# BatteryBoard.net
KiCad netlist of a schematic drawn in Altium Designer
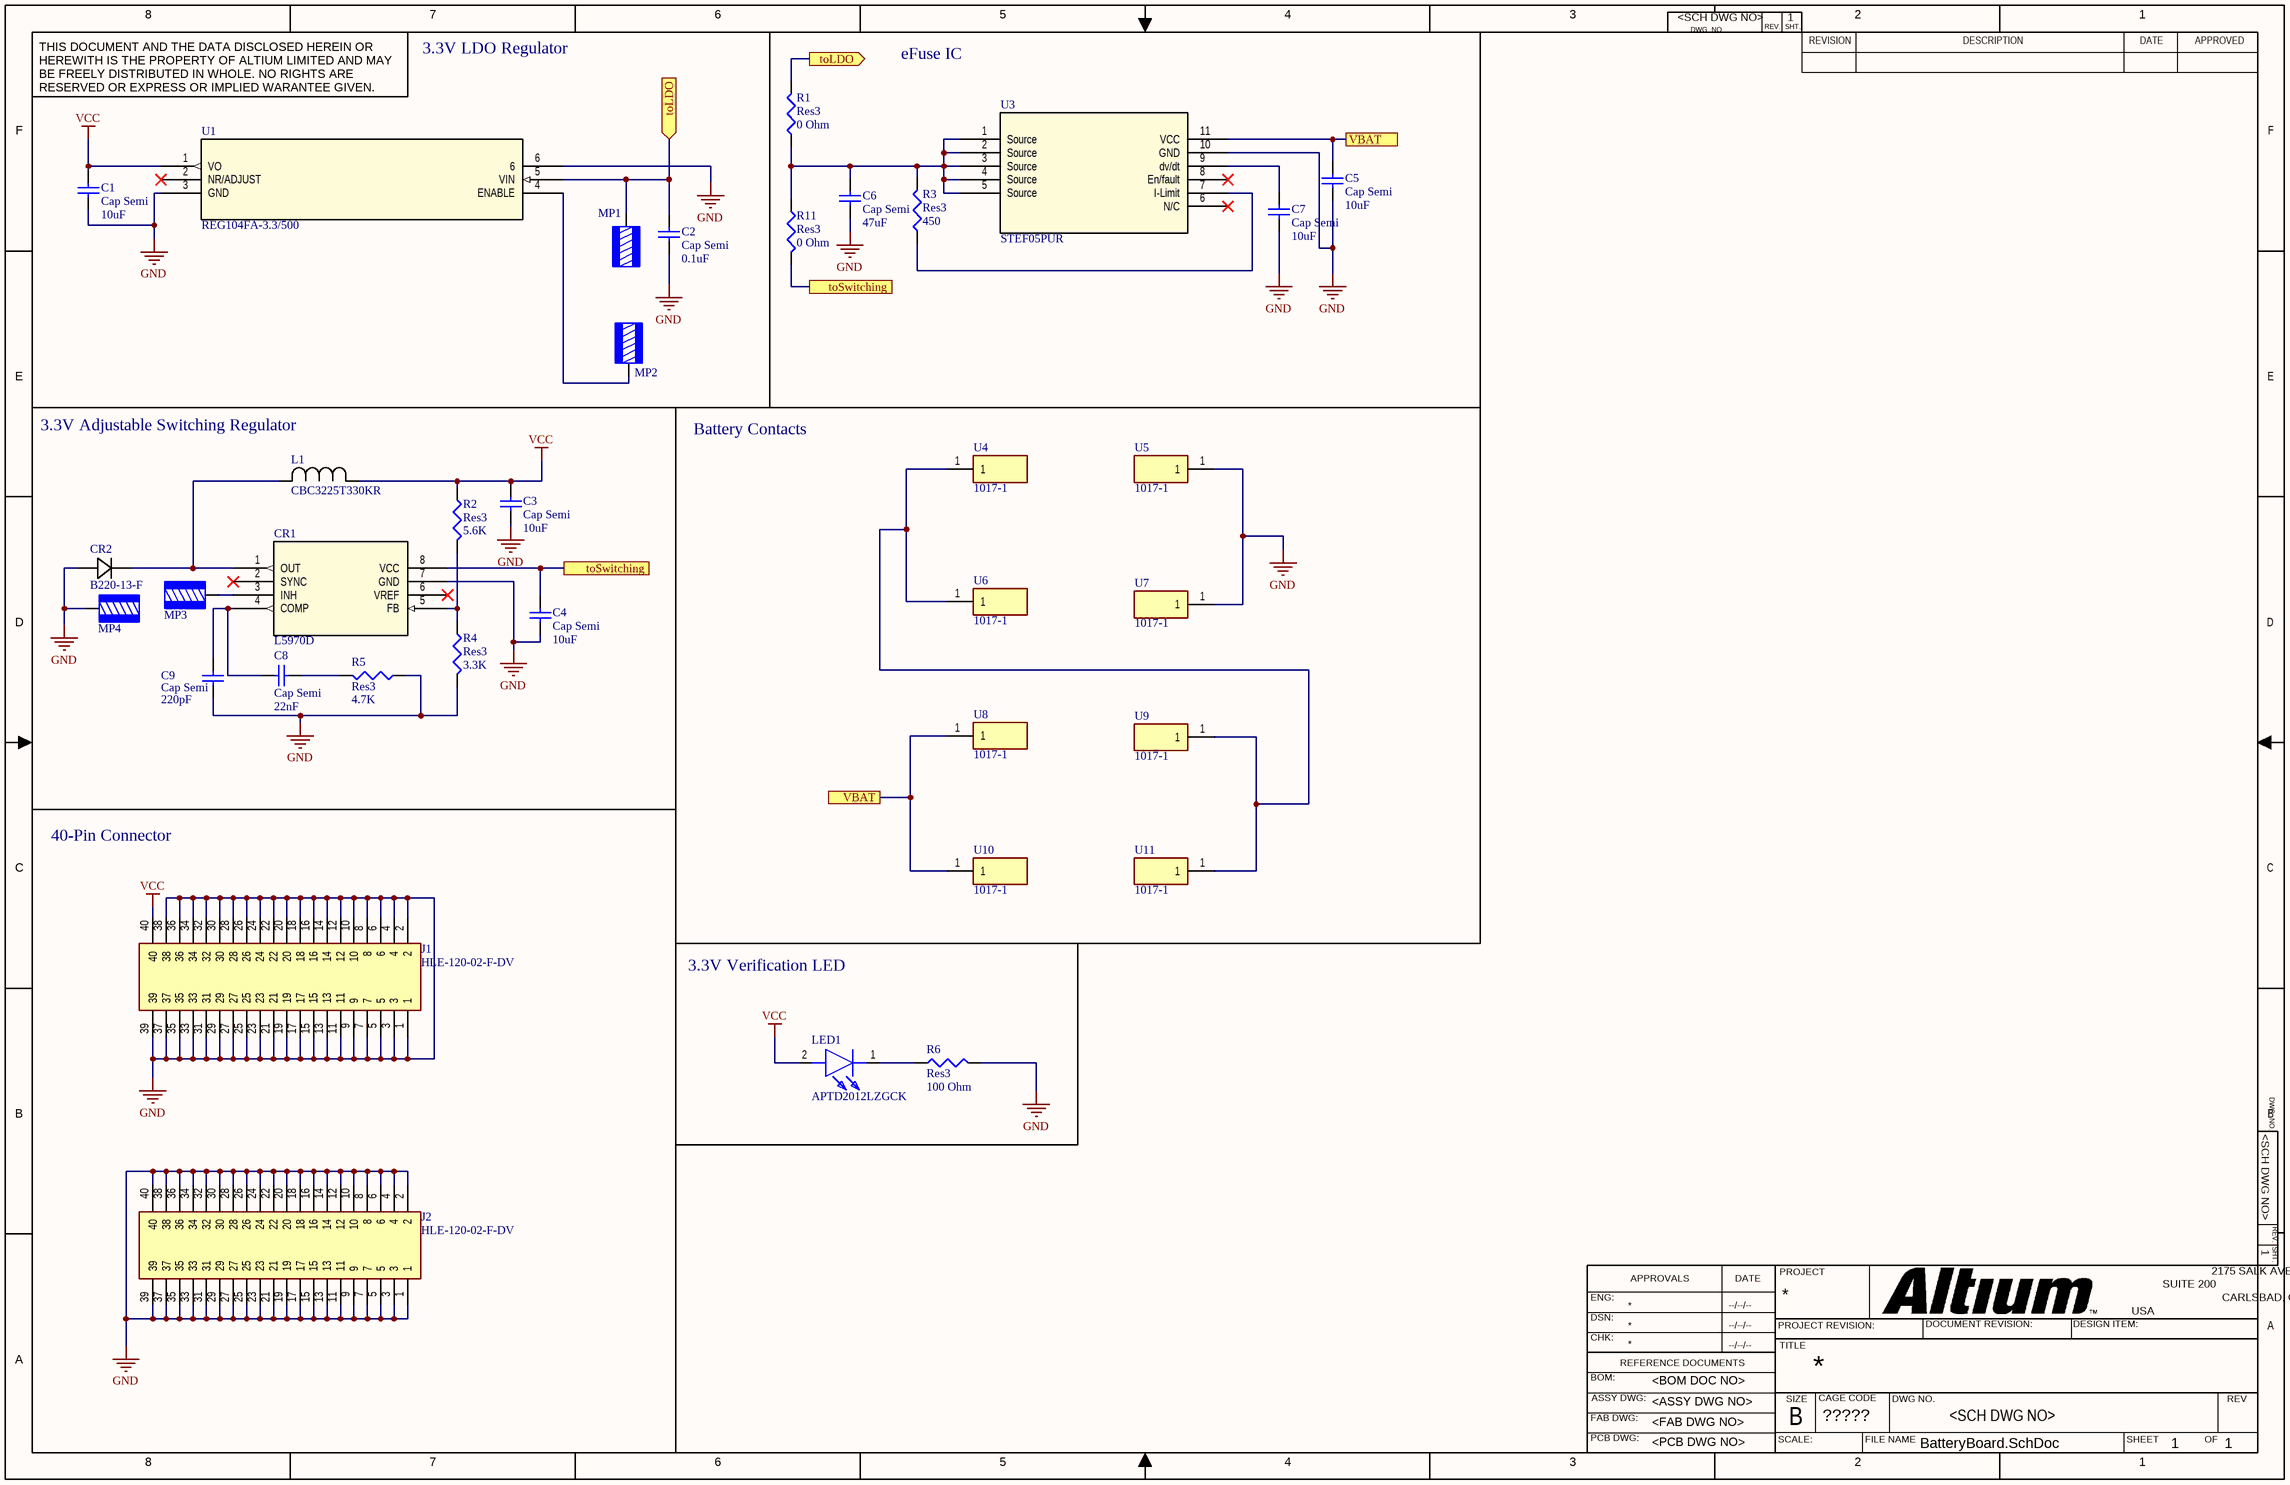
[diagram p0: BatteryBoard.SchDoc]

(export (version "E")
  (design (tool "Eeschema 10.0.6"))
  (components
    (comp (ref "C1")
      (value "Cap Semi")
      (footprint "C1206")
      (description "Capacitor (Semiconductor SIM Model)")
      (fields (field (name "ALTIUM_VALUE") "10uF") (field (name "PUBLISHER") "Altium Limited"))
      (libsource (lib "Miscellaneous Devices") (part "Cap Semi"))
    )
    (comp (ref "C2")
      (value "Cap Semi")
      (footprint "C1206")
      (description "Capacitor (Semiconductor SIM Model)")
      (fields (field (name "ALTIUM_VALUE") "0.1uF") (field (name "PUBLISHER") "Altium Limited"))
      (libsource (lib "Miscellaneous Devices") (part "Cap Semi"))
    )
    (comp (ref "C3")
      (value "Cap Semi")
      (footprint "C1206")
      (description "Capacitor (Semiconductor SIM Model)")
      (fields (field (name "ALTIUM_VALUE") "10uF") (field (name "PUBLISHER") "Altium Limited"))
      (libsource (lib "Miscellaneous Devices") (part "Cap Semi"))
    )
    (comp (ref "C4")
      (value "Cap Semi")
      (footprint "C1206")
      (description "Capacitor (Semiconductor SIM Model)")
      (fields (field (name "ALTIUM_VALUE") "10uF") (field (name "PUBLISHER") "Altium Limited"))
      (libsource (lib "Miscellaneous Devices") (part "Cap Semi"))
    )
    (comp (ref "C5")
      (value "Cap Semi")
      (footprint "C1206")
      (description "Capacitor (Semiconductor SIM Model)")
      (fields (field (name "ALTIUM_VALUE") "10uF") (field (name "PUBLISHER") "Altium Limited"))
      (libsource (lib "Miscellaneous Devices") (part "Cap Semi"))
    )
    (comp (ref "C6")
      (value "Cap Semi")
      (footprint "C1206")
      (description "Capacitor (Semiconductor SIM Model)")
      (fields (field (name "ALTIUM_VALUE") "47uF") (field (name "PUBLISHER") "Altium Limited"))
      (libsource (lib "Miscellaneous Devices") (part "Cap Semi"))
    )
    (comp (ref "C7")
      (value "Cap Semi")
      (footprint "C1206")
      (description "Capacitor (Semiconductor SIM Model)")
      (fields (field (name "ALTIUM_VALUE") "10uF") (field (name "PUBLISHER") "Altium Limited"))
      (libsource (lib "Miscellaneous Devices") (part "Cap Semi"))
    )
    (comp (ref "C8")
      (value "Cap Semi")
      (footprint "C1206")
      (description "Capacitor (Semiconductor SIM Model)")
      (fields (field (name "ALTIUM_VALUE") "22nF") (field (name "PUBLISHER") "Altium Limited"))
      (libsource (lib "Miscellaneous Devices") (part "Cap Semi"))
    )
    (comp (ref "C9")
      (value "Cap Semi")
      (footprint "C1206")
      (description "Capacitor (Semiconductor SIM Model)")
      (fields (field (name "ALTIUM_VALUE") "220pF") (field (name "PUBLISHER") "Altium Limited"))
      (libsource (lib "Miscellaneous Devices") (part "Cap Semi"))
    )
    (comp (ref "CR1")
      (value "L5970D")
      (footprint "SO-8_STM-M")
      (description "No Description Available")
      (fields (field (name "COPYRIGHT") "Copyright (C) 2022 Ultra Librarian. All rights reserved."))
      (libsource (lib "L5970D") (part "L5970D"))
    )
    (comp (ref "CR2")
      (value "B220-13-F")
      (footprint "SMB_DIO")
      (description "No Description Available")
      (fields (field (name "COPYRIGHT") "Copyright (C) 2022 Ultra Librarian. All rights reserved."))
      (libsource (lib "B220-13-F") (part "B220-13-F"))
    )
    (comp (ref "J1")
      (value "HLE-120-02-F-DV")
      (footprint "SAMTEC_HLE-120-02-F-DV")
      (description "Connector")
      (libsource (lib "*") (part "HLE-120-02-F-DV"))
    )
    (comp (ref "J2")
      (value "HLE-120-02-F-DV")
      (footprint "SAMTEC_HLE-120-02-F-DV")
      (description "Connector")
      (libsource (lib "*") (part "HLE-120-02-F-DV"))
    )
    (comp (ref "L1")
      (value "CBC3225T330KR")
      (footprint "IND_TAIYO_CBC3225_TAY")
      (description "No Description Available")
      (fields (field (name "COPYRIGHT") "Copyright (C) 2022 Ultra Librarian. All rights reserved."))
      (libsource (lib "CBC3225T330KR") (part "CBC3225T330KR"))
    )
    (comp (ref "LED1")
      (value "APTD2012LZGCK")
      (footprint "SamacSys:LEDC2012X105N")
      (description "LED")
      (fields (field (name "MOUSER2 PART NUMBER") "604-APTD2012LZGCK"))
      (libsource (lib "*") (part "APTD2012LZGCK"))
    )
    (comp (ref "MP1")
      (value "M3")
      (footprint "7466303")
      (description "WP-SMRA REDCUBE SMT Right Angled without pins, M3, 50A")
      (fields
        (field (name "MANUFACTURER PART NUMBER") "7466303")
        (field (name "MANUFACTURER") "Wurth Elektronik")
      )
      (libsource (lib "WP-SMRA") (part "7466303"))
    )
    (comp (ref "MP2")
      (value "M3")
      (footprint "7466303")
      (description "WP-SMRA REDCUBE SMT Right Angled without pins, M3, 50A")
      (fields
        (field (name "MANUFACTURER PART NUMBER") "7466303")
        (field (name "MANUFACTURER") "Wurth Elektronik")
      )
      (libsource (lib "WP-SMRA") (part "7466303"))
    )
    (comp (ref "MP3")
      (value "M3")
      (footprint "7466303")
      (description "WP-SMRA REDCUBE SMT Right Angled without pins, M3, 50A")
      (fields
        (field (name "MANUFACTURER PART NUMBER") "7466303")
        (field (name "MANUFACTURER") "Wurth Elektronik")
      )
      (libsource (lib "WP-SMRA") (part "7466303"))
    )
    (comp (ref "MP4")
      (value "M3")
      (footprint "7466303")
      (description "WP-SMRA REDCUBE SMT Right Angled without pins, M3, 50A")
      (fields
        (field (name "MANUFACTURER PART NUMBER") "7466303")
        (field (name "MANUFACTURER") "Wurth Elektronik")
      )
      (libsource (lib "WP-SMRA") (part "7466303"))
    )
    (comp (ref "R1")
      (value "Res3")
      (footprint "J1-0603")
      (description "Resistor")
      (fields (field (name "ALTIUM_VALUE") "0 Ohm") (field (name "PUBLISHER") "Altium Limited"))
      (libsource (lib "Miscellaneous Devices") (part "Res3"))
    )
    (comp (ref "R2")
      (value "Res3")
      (footprint "J1-0603")
      (description "Resistor")
      (fields (field (name "ALTIUM_VALUE") "5.6K") (field (name "PUBLISHER") "Altium Limited"))
      (libsource (lib "Miscellaneous Devices") (part "Res3"))
    )
    (comp (ref "R3")
      (value "Res3")
      (footprint "J1-0603")
      (description "Resistor")
      (fields (field (name "ALTIUM_VALUE") "450") (field (name "PUBLISHER") "Altium Limited"))
      (libsource (lib "Miscellaneous Devices") (part "Res3"))
    )
    (comp (ref "R4")
      (value "Res3")
      (footprint "J1-0603")
      (description "Resistor")
      (fields (field (name "ALTIUM_VALUE") "3.3K") (field (name "PUBLISHER") "Altium Limited"))
      (libsource (lib "Miscellaneous Devices") (part "Res3"))
    )
    (comp (ref "R5")
      (value "Res3")
      (footprint "J1-0603")
      (description "Resistor")
      (fields (field (name "ALTIUM_VALUE") "4.7K") (field (name "PUBLISHER") "Altium Limited"))
      (libsource (lib "Miscellaneous Devices") (part "Res3"))
    )
    (comp (ref "R6")
      (value "Res3")
      (footprint "J1-0603")
      (description "Resistor")
      (fields (field (name "ALTIUM_VALUE") "100 Ohm") (field (name "PUBLISHER") "Altium Limited"))
      (libsource (lib "Miscellaneous Devices") (part "Res3"))
    )
    (comp (ref "R11")
      (value "Res3")
      (footprint "J1-0603")
      (description "Resistor")
      (fields (field (name "ALTIUM_VALUE") "0 Ohm") (field (name "PUBLISHER") "Altium Limited"))
      (libsource (lib "Miscellaneous Devices") (part "Res3"))
    )
    (comp (ref "U1")
      (value "REG104FA-3.3/500")
      (footprint "KTT5_TEX")
      (description "No Description Available")
      (fields (field (name "COPYRIGHT") "Copyright (C) 2022 Ultra Librarian. All rights reserved."))
      (libsource (lib "REG104FA-3P3&slash_500") (part "REG104FA-3.3/500"))
    )
    (comp (ref "U3")
      (value "STEF05PUR")
      (footprint "DFN_EF05PUR_STM")
      (description "No Description Available")
      (fields (field (name "COPYRIGHT") "Copyright (C) 2022 Ultra Librarian. All rights reserved."))
      (libsource (lib "STEF05PUR") (part "STEF05PUR"))
    )
    (comp (ref "U4")
      (value "1017-1")
      (footprint "SamacSys:10171")
      (description "Undefined or Miscellaneous")
      (fields (field (name "MOUSER PART NUMBER") "534-1017-1"))
      (libsource (lib "") (part "1017-1_1"))
    )
    (comp (ref "U5")
      (value "1017-1")
      (footprint "SamacSys:10171")
      (description "Undefined or Miscellaneous")
      (fields (field (name "MOUSER PART NUMBER") "534-1017-1"))
      (libsource (lib "SamacSys") (part "1017-1"))
    )
    (comp (ref "U6")
      (value "1017-1")
      (footprint "SamacSys:10171")
      (description "Undefined or Miscellaneous")
      (fields (field (name "MOUSER PART NUMBER") "534-1017-1"))
      (libsource (lib "") (part "1017-1_1"))
    )
    (comp (ref "U7")
      (value "1017-1")
      (footprint "SamacSys:10171")
      (description "Undefined or Miscellaneous")
      (fields (field (name "MOUSER PART NUMBER") "534-1017-1"))
      (libsource (lib "SamacSys") (part "1017-1"))
    )
    (comp (ref "U8")
      (value "1017-1")
      (footprint "SamacSys:10171")
      (description "Undefined or Miscellaneous")
      (fields (field (name "MOUSER PART NUMBER") "534-1017-1"))
      (libsource (lib "") (part "1017-1_1"))
    )
    (comp (ref "U9")
      (value "1017-1")
      (footprint "SamacSys:10171")
      (description "Undefined or Miscellaneous")
      (fields (field (name "MOUSER PART NUMBER") "534-1017-1"))
      (libsource (lib "SamacSys") (part "1017-1"))
    )
    (comp (ref "U10")
      (value "1017-1")
      (footprint "SamacSys:10171")
      (description "Undefined or Miscellaneous")
      (fields (field (name "MOUSER PART NUMBER") "534-1017-1"))
      (libsource (lib "") (part "1017-1_1"))
    )
    (comp (ref "U11")
      (value "1017-1")
      (footprint "SamacSys:10171")
      (description "Undefined or Miscellaneous")
      (fields (field (name "MOUSER PART NUMBER") "534-1017-1"))
      (libsource (lib "SamacSys") (part "1017-1"))
    )
  )
  (nets
    (net (code "1") (name "/VBAT") (class "Default")
      (node (ref "C5") (pin "1") (pinfunction "1_1") (pintype "passive"))
      (node (ref "U10") (pin "1") (pinfunction "1_1") (pintype "passive"))
      (node (ref "U3") (pin "11") (pinfunction "VCC_11") (pintype "power_in"))
      (node (ref "U8") (pin "1") (pinfunction "1_1") (pintype "passive"))
    )
    (net (code "2") (name "/toLDO") (class "Default")
      (node (ref "C2") (pin "2") (pinfunction "2_2") (pintype "passive"))
      (node (ref "MP1") (pin "1") (pinfunction "1_1") (pintype "passive"))
      (node (ref "R1") (pin "2") (pinfunction "2_2") (pintype "passive"))
      (node (ref "U1") (pin "5") (pinfunction "VIN_5") (pintype "input"))
    )
    (net (code "3") (name "/toSwitching") (class "Default")
      (node (ref "C4") (pin "2") (pinfunction "2_2") (pintype "passive"))
      (node (ref "CR1") (pin "8") (pinfunction "VCC_8") (pintype "power_in"))
      (node (ref "R11") (pin "2") (pinfunction "2_2") (pintype "passive"))
    )
    (net (code "4") (name "GND") (class "Default")
      (node (ref "C1") (pin "1") (pinfunction "1_1") (pintype "passive"))
      (node (ref "C2") (pin "1") (pinfunction "1_1") (pintype "passive"))
      (node (ref "C3") (pin "1") (pinfunction "1_1") (pintype "passive"))
      (node (ref "C4") (pin "1") (pinfunction "1_1") (pintype "passive"))
      (node (ref "C5") (pin "2") (pinfunction "2_2") (pintype "passive"))
      (node (ref "C6") (pin "2") (pinfunction "2_2") (pintype "passive"))
      (node (ref "C7") (pin "2") (pinfunction "2_2") (pintype "passive"))
      (node (ref "C9") (pin "1") (pinfunction "1_1") (pintype "passive"))
      (node (ref "CR1") (pin "7") (pinfunction "GND_7") (pintype "power_in"))
      (node (ref "CR2") (pin "2") (pinfunction "2_2") (pintype "passive"))
      (node (ref "J1") (pin "1") (pinfunction "1_1") (pintype "passive"))
      (node (ref "J1") (pin "10") (pinfunction "10_10") (pintype "passive"))
      (node (ref "J1") (pin "11") (pinfunction "11_11") (pintype "passive"))
      (node (ref "J1") (pin "12") (pinfunction "12_12") (pintype "passive"))
      (node (ref "J1") (pin "13") (pinfunction "13_13") (pintype "passive"))
      (node (ref "J1") (pin "14") (pinfunction "14_14") (pintype "passive"))
      (node (ref "J1") (pin "15") (pinfunction "15_15") (pintype "passive"))
      (node (ref "J1") (pin "16") (pinfunction "16_16") (pintype "passive"))
      (node (ref "J1") (pin "17") (pinfunction "17_17") (pintype "passive"))
      (node (ref "J1") (pin "18") (pinfunction "18_18") (pintype "passive"))
      (node (ref "J1") (pin "19") (pinfunction "19_19") (pintype "passive"))
      (node (ref "J1") (pin "2") (pinfunction "2_2") (pintype "passive"))
      (node (ref "J1") (pin "20") (pinfunction "20_20") (pintype "passive"))
      (node (ref "J1") (pin "21") (pinfunction "21_21") (pintype "passive"))
      (node (ref "J1") (pin "22") (pinfunction "22_22") (pintype "passive"))
      (node (ref "J1") (pin "23") (pinfunction "23_23") (pintype "passive"))
      (node (ref "J1") (pin "24") (pinfunction "24_24") (pintype "passive"))
      (node (ref "J1") (pin "25") (pinfunction "25_25") (pintype "passive"))
      (node (ref "J1") (pin "26") (pinfunction "26_26") (pintype "passive"))
      (node (ref "J1") (pin "27") (pinfunction "27_27") (pintype "passive"))
      (node (ref "J1") (pin "28") (pinfunction "28_28") (pintype "passive"))
      (node (ref "J1") (pin "29") (pinfunction "29_29") (pintype "passive"))
      (node (ref "J1") (pin "3") (pinfunction "3_3") (pintype "passive"))
      (node (ref "J1") (pin "30") (pinfunction "30_30") (pintype "passive"))
      (node (ref "J1") (pin "31") (pinfunction "31_31") (pintype "passive"))
      (node (ref "J1") (pin "32") (pinfunction "32_32") (pintype "passive"))
      (node (ref "J1") (pin "33") (pinfunction "33_33") (pintype "passive"))
      (node (ref "J1") (pin "34") (pinfunction "34_34") (pintype "passive"))
      (node (ref "J1") (pin "35") (pinfunction "35_35") (pintype "passive"))
      (node (ref "J1") (pin "36") (pinfunction "36_36") (pintype "passive"))
      (node (ref "J1") (pin "37") (pinfunction "37_37") (pintype "passive"))
      (node (ref "J1") (pin "38") (pinfunction "38_38") (pintype "passive"))
      (node (ref "J1") (pin "39") (pinfunction "39_39") (pintype "passive"))
      (node (ref "J1") (pin "4") (pinfunction "4_4") (pintype "passive"))
      (node (ref "J1") (pin "5") (pinfunction "5_5") (pintype "passive"))
      (node (ref "J1") (pin "6") (pinfunction "6_6") (pintype "passive"))
      (node (ref "J1") (pin "7") (pinfunction "7_7") (pintype "passive"))
      (node (ref "J1") (pin "8") (pinfunction "8_8") (pintype "passive"))
      (node (ref "J1") (pin "9") (pinfunction "9_9") (pintype "passive"))
      (node (ref "J2") (pin "1") (pinfunction "1_1") (pintype "passive"))
      (node (ref "J2") (pin "10") (pinfunction "10_10") (pintype "passive"))
      (node (ref "J2") (pin "11") (pinfunction "11_11") (pintype "passive"))
      (node (ref "J2") (pin "12") (pinfunction "12_12") (pintype "passive"))
      (node (ref "J2") (pin "13") (pinfunction "13_13") (pintype "passive"))
      (node (ref "J2") (pin "14") (pinfunction "14_14") (pintype "passive"))
      (node (ref "J2") (pin "15") (pinfunction "15_15") (pintype "passive"))
      (node (ref "J2") (pin "16") (pinfunction "16_16") (pintype "passive"))
      (node (ref "J2") (pin "17") (pinfunction "17_17") (pintype "passive"))
      (node (ref "J2") (pin "18") (pinfunction "18_18") (pintype "passive"))
      (node (ref "J2") (pin "19") (pinfunction "19_19") (pintype "passive"))
      (node (ref "J2") (pin "2") (pinfunction "2_2") (pintype "passive"))
      (node (ref "J2") (pin "20") (pinfunction "20_20") (pintype "passive"))
      (node (ref "J2") (pin "21") (pinfunction "21_21") (pintype "passive"))
      (node (ref "J2") (pin "22") (pinfunction "22_22") (pintype "passive"))
      (node (ref "J2") (pin "23") (pinfunction "23_23") (pintype "passive"))
      (node (ref "J2") (pin "24") (pinfunction "24_24") (pintype "passive"))
      (node (ref "J2") (pin "25") (pinfunction "25_25") (pintype "passive"))
      (node (ref "J2") (pin "26") (pinfunction "26_26") (pintype "passive"))
      (node (ref "J2") (pin "27") (pinfunction "27_27") (pintype "passive"))
      (node (ref "J2") (pin "28") (pinfunction "28_28") (pintype "passive"))
      (node (ref "J2") (pin "29") (pinfunction "29_29") (pintype "passive"))
      (node (ref "J2") (pin "3") (pinfunction "3_3") (pintype "passive"))
      (node (ref "J2") (pin "30") (pinfunction "30_30") (pintype "passive"))
      (node (ref "J2") (pin "31") (pinfunction "31_31") (pintype "passive"))
      (node (ref "J2") (pin "32") (pinfunction "32_32") (pintype "passive"))
      (node (ref "J2") (pin "33") (pinfunction "33_33") (pintype "passive"))
      (node (ref "J2") (pin "34") (pinfunction "34_34") (pintype "passive"))
      (node (ref "J2") (pin "35") (pinfunction "35_35") (pintype "passive"))
      (node (ref "J2") (pin "36") (pinfunction "36_36") (pintype "passive"))
      (node (ref "J2") (pin "37") (pinfunction "37_37") (pintype "passive"))
      (node (ref "J2") (pin "38") (pinfunction "38_38") (pintype "passive"))
      (node (ref "J2") (pin "39") (pinfunction "39_39") (pintype "passive"))
      (node (ref "J2") (pin "4") (pinfunction "4_4") (pintype "passive"))
      (node (ref "J2") (pin "40") (pinfunction "40_40") (pintype "passive"))
      (node (ref "J2") (pin "5") (pinfunction "5_5") (pintype "passive"))
      (node (ref "J2") (pin "6") (pinfunction "6_6") (pintype "passive"))
      (node (ref "J2") (pin "7") (pinfunction "7_7") (pintype "passive"))
      (node (ref "J2") (pin "8") (pinfunction "8_8") (pintype "passive"))
      (node (ref "J2") (pin "9") (pinfunction "9_9") (pintype "passive"))
      (node (ref "MP4") (pin "1") (pinfunction "1_1") (pintype "passive"))
      (node (ref "R4") (pin "2") (pinfunction "2_2") (pintype "passive"))
      (node (ref "R5") (pin "1") (pinfunction "1_1") (pintype "passive"))
      (node (ref "R6") (pin "2") (pinfunction "2_2") (pintype "passive"))
      (node (ref "U1") (pin "3") (pinfunction "GND_3") (pintype "power_in"))
      (node (ref "U1") (pin "6") (pinfunction "6_6") (pintype "passive"))
      (node (ref "U3") (pin "10") (pinfunction "GND_10") (pintype "passive"))
      (node (ref "U5") (pin "1") (pinfunction "1_1") (pintype "passive"))
      (node (ref "U7") (pin "1") (pinfunction "1_1") (pintype "passive"))
    )
    (net (code "5") (name "Net-(C6-Pad1)") (class "Default")
      (node (ref "C6") (pin "1") (pinfunction "1_1") (pintype "passive"))
      (node (ref "R1") (pin "1") (pinfunction "1_1") (pintype "passive"))
      (node (ref "R11") (pin "1") (pinfunction "1_1") (pintype "passive"))
      (node (ref "R3") (pin "2") (pinfunction "2_2") (pintype "passive"))
      (node (ref "U3") (pin "1") (pinfunction "Source_1") (pintype "passive"))
      (node (ref "U3") (pin "2") (pinfunction "Source_2") (pintype "passive"))
      (node (ref "U3") (pin "3") (pinfunction "Source_3") (pintype "passive"))
      (node (ref "U3") (pin "4") (pinfunction "Source_4") (pintype "passive"))
      (node (ref "U3") (pin "5") (pinfunction "Source_5") (pintype "passive"))
    )
    (net (code "6") (name "Net-(C8-Pad1)") (class "Default")
      (node (ref "C8") (pin "1") (pinfunction "1_1") (pintype "passive"))
      (node (ref "R5") (pin "2") (pinfunction "2_2") (pintype "passive"))
    )
    (net (code "7") (name "Net-(CR1-COMP)") (class "Default")
      (node (ref "C8") (pin "2") (pinfunction "2_2") (pintype "passive"))
      (node (ref "C9") (pin "2") (pinfunction "2_2") (pintype "passive"))
      (node (ref "CR1") (pin "4") (pinfunction "COMP_4") (pintype "output"))
    )
    (net (code "8") (name "Net-(CR1-FB)") (class "Default")
      (node (ref "CR1") (pin "5") (pinfunction "FB_5") (pintype "input"))
      (node (ref "R2") (pin "2") (pinfunction "2_2") (pintype "passive"))
      (node (ref "R4") (pin "1") (pinfunction "1_1") (pintype "passive"))
    )
    (net (code "9") (name "Net-(CR1-INH)") (class "Default")
      (node (ref "CR1") (pin "3") (pinfunction "INH_3") (pintype "passive"))
      (node (ref "MP3") (pin "1") (pinfunction "1_1") (pintype "passive"))
    )
    (net (code "10") (name "Net-(CR1-OUT)") (class "Default")
      (node (ref "CR1") (pin "1") (pinfunction "OUT_1") (pintype "output"))
      (node (ref "CR2") (pin "1") (pinfunction "1_1") (pintype "passive"))
      (node (ref "L1") (pin "2") (pinfunction "2_2") (pintype "passive"))
    )
    (net (code "11") (name "Net-(LED1-K)") (class "Default")
      (node (ref "LED1") (pin "1") (pinfunction "K_1") (pintype "passive"))
      (node (ref "R6") (pin "1") (pinfunction "1_1") (pintype "passive"))
    )
    (net (code "12") (name "Net-(U1-ENABLE)") (class "Default")
      (node (ref "MP2") (pin "1") (pinfunction "1_1") (pintype "passive"))
      (node (ref "U1") (pin "4") (pinfunction "ENABLE_4") (pintype "passive"))
    )
    (net (code "13") (name "Net-(U3-I-Limit)") (class "Default")
      (node (ref "R3") (pin "1") (pinfunction "1_1") (pintype "passive"))
      (node (ref "U3") (pin "7") (pinfunction "I-Limit_7") (pintype "passive"))
    )
    (net (code "14") (name "Net-(U3-dv{slash}dt)") (class "Default")
      (node (ref "C7") (pin "1") (pinfunction "1_1") (pintype "passive"))
      (node (ref "U3") (pin "9") (pinfunction "dv/dt_9") (pintype "passive"))
    )
    (net (code "15") (name "Net-(U11-Pad1)") (class "Default")
      (node (ref "U11") (pin "1") (pinfunction "1_1") (pintype "passive"))
      (node (ref "U4") (pin "1") (pinfunction "1_1") (pintype "passive"))
      (node (ref "U6") (pin "1") (pinfunction "1_1") (pintype "passive"))
      (node (ref "U9") (pin "1") (pinfunction "1_1") (pintype "passive"))
    )
    (net (code "16") (name "VCC") (class "Default")
      (node (ref "C1") (pin "2") (pinfunction "2_2") (pintype "passive"))
      (node (ref "C3") (pin "2") (pinfunction "2_2") (pintype "passive"))
      (node (ref "J1") (pin "40") (pinfunction "40_40") (pintype "passive"))
      (node (ref "L1") (pin "1") (pinfunction "1_1") (pintype "passive"))
      (node (ref "LED1") (pin "2") (pinfunction "A_2") (pintype "passive"))
      (node (ref "R2") (pin "1") (pinfunction "1_1") (pintype "passive"))
      (node (ref "U1") (pin "1") (pinfunction "VO_1") (pintype "output"))
    )
    (net (code "17") (name "unconnected-(CR1-SYNC-Pad2)") (class "Default")
      (node (ref "CR1") (pin "2") (pinfunction "SYNC_2") (pintype "passive+no_connect"))
    )
    (net (code "18") (name "unconnected-(CR1-VREF-Pad6)") (class "Default")
      (node (ref "CR1") (pin "6") (pinfunction "VREF_6") (pintype "power_in+no_connect"))
    )
    (net (code "19") (name "unconnected-(U1-NR{slash}ADJUST-Pad2)") (class "Default")
      (node (ref "U1") (pin "2") (pinfunction "NR/ADJUST_2") (pintype "passive+no_connect"))
    )
    (net (code "20") (name "unconnected-(U3-En{slash}fault-Pad8)") (class "Default")
      (node (ref "U3") (pin "8") (pinfunction "En/fault_8") (pintype "passive+no_connect"))
    )
    (net (code "21") (name "unconnected-(U3-N{slash}C-Pad6)") (class "Default")
      (node (ref "U3") (pin "6") (pinfunction "N/C_6") (pintype "passive+no_connect"))
    )
  )
)
